# XTX.net
KiCad netlist of a schematic drawn in Altium Designer
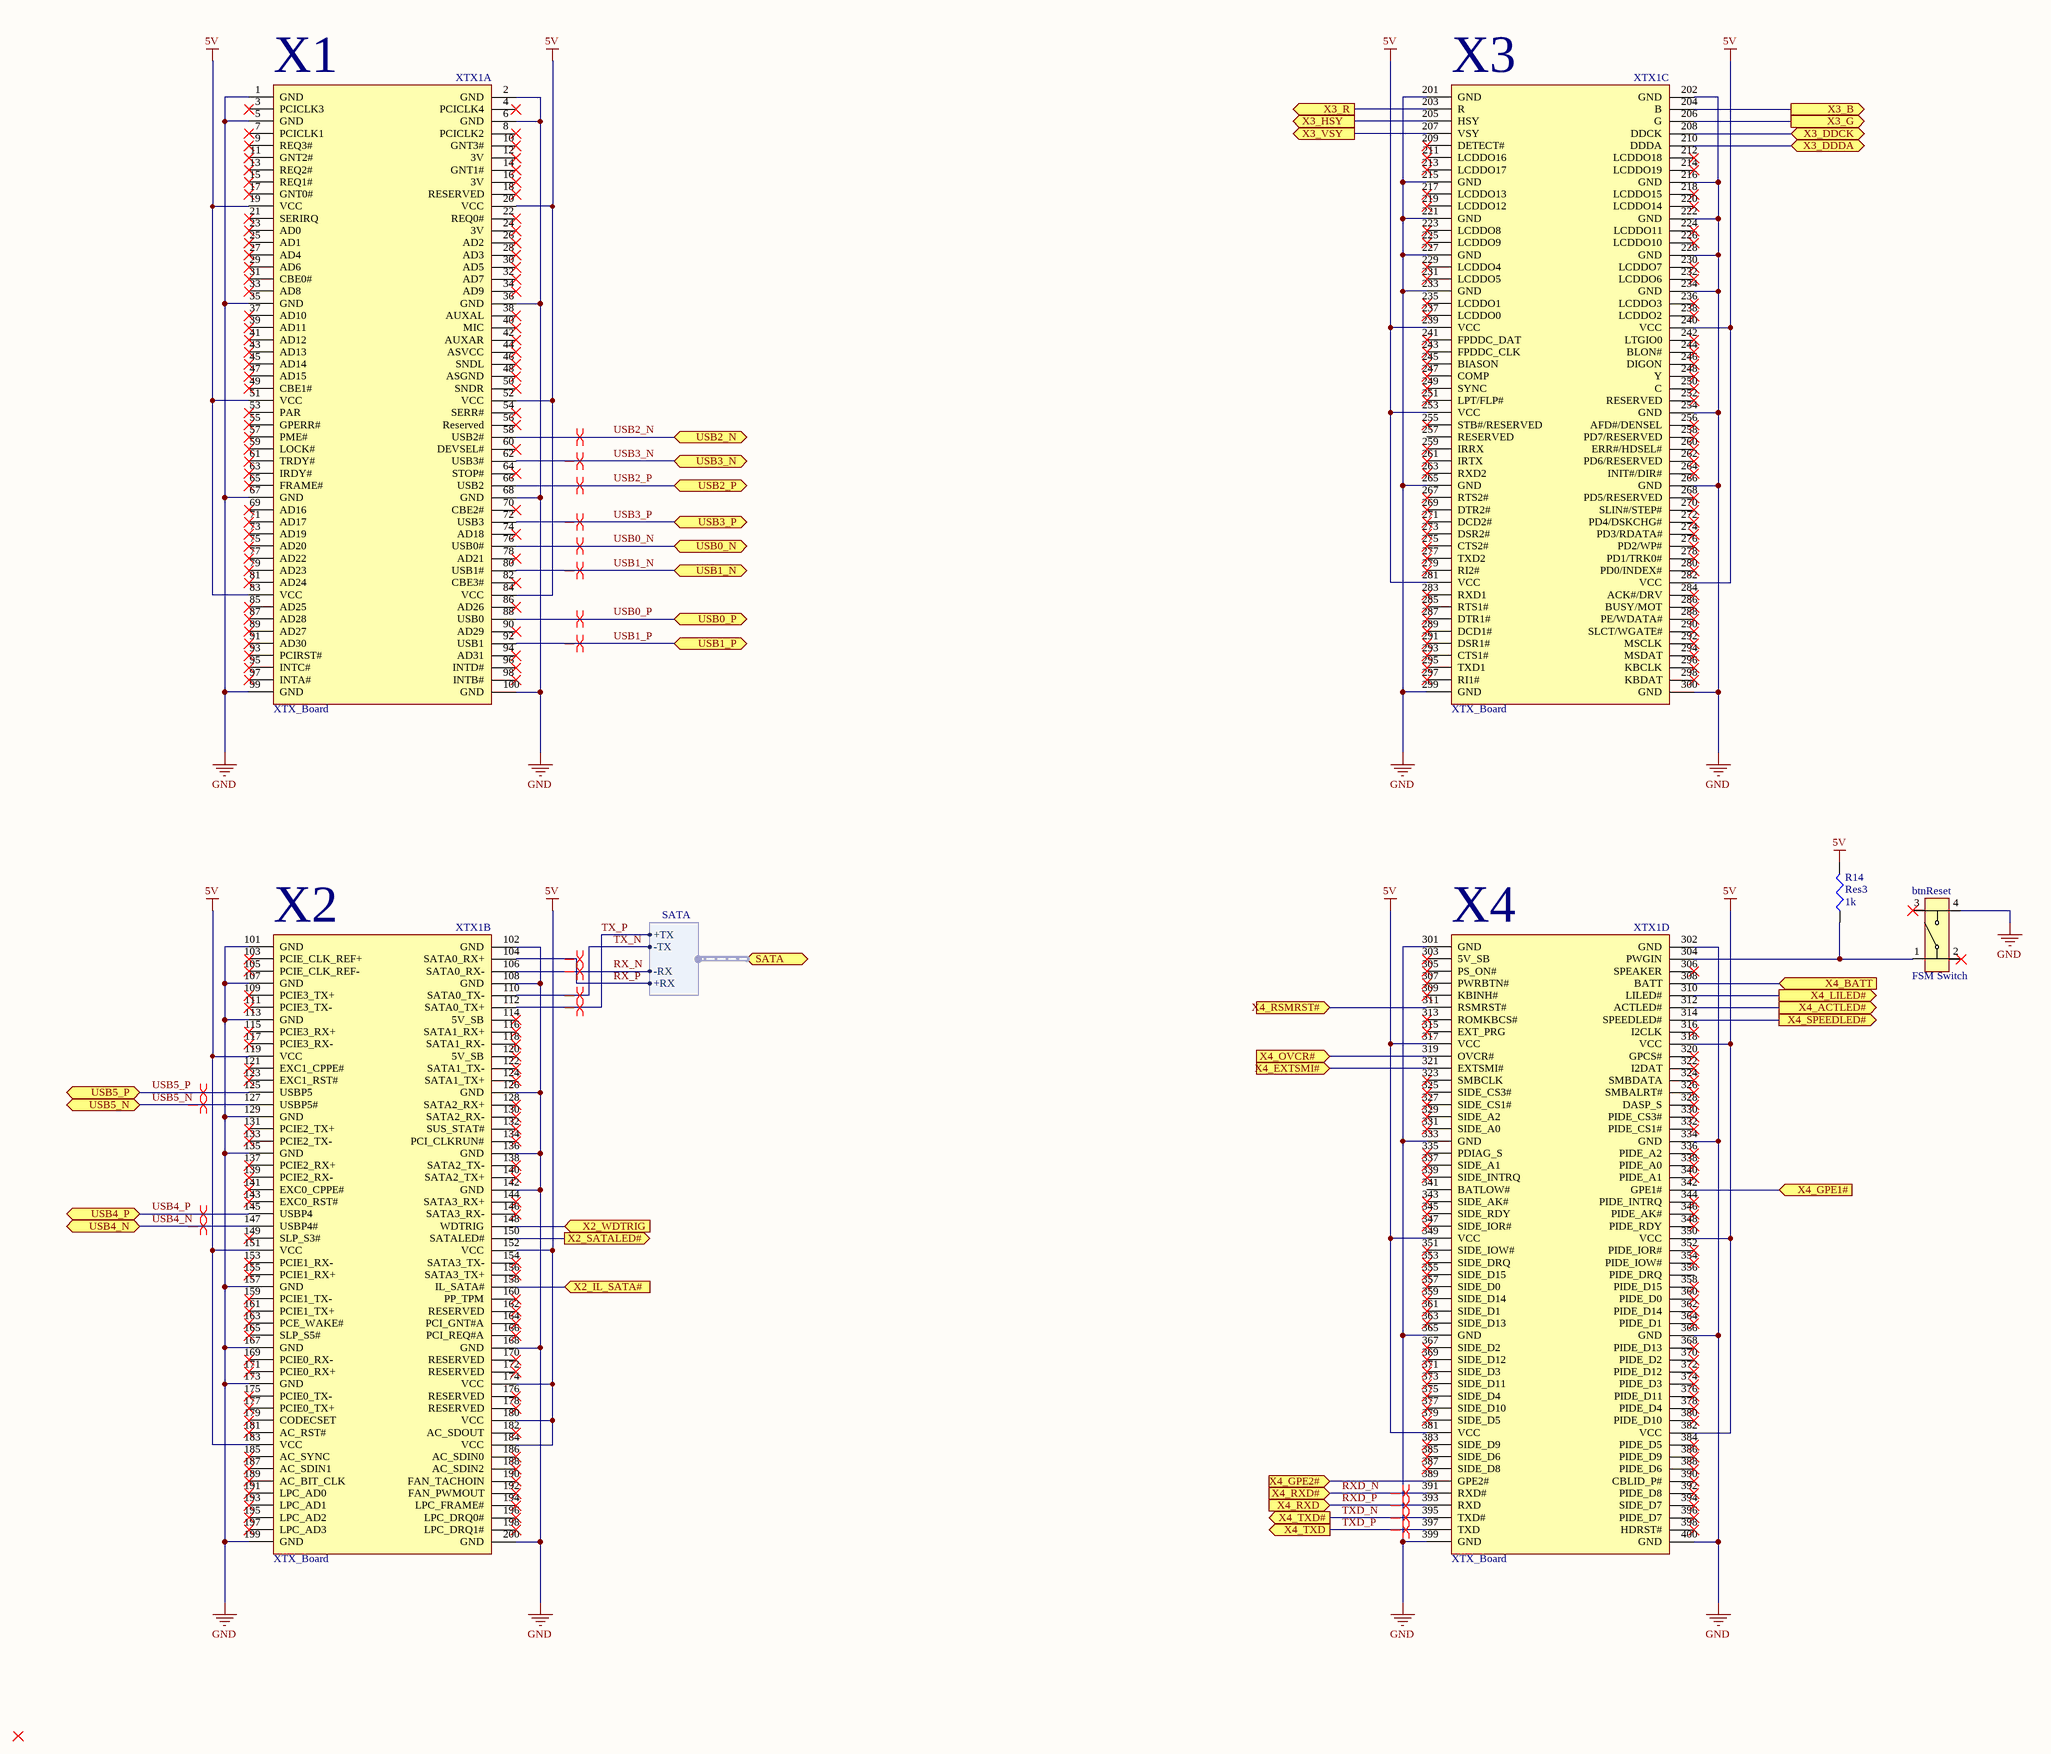
[diagram p0: XTX.SchDoc]

(export (version "E")
  (design (tool "Eeschema 10.0.6"))
  (components
    (comp (ref "btnReset")
      (value "FSM Switch")
      (footprint "FSM4JH")
      (description "FSM 6mm Series Switch")
      (libsource (lib "Buttons") (part "FSM Switch"))
    )
    (comp (ref "R14")
      (value "Res3")
      (footprint "J1-0603")
      (description "Resistor")
      (fields (field (name "ALTIUM_VALUE") "1k") (field (name "PUBLISHER") "Altium Limited"))
      (libsource (lib "Miscellaneous Devices") (part "Res3"))
    )
    (comp (ref "XTX1") (value "XTX_Board") (footprint "XTX_Board") (libsource (lib "XTX") (part "XTX_Board")))
  )
  (nets
    (net (code "2") (name "/RXD_N") (class "Default")
      (node (ref "XTX1") (pin "391") (pinfunction "RXD#_391") (pintype "passive"))
    )
    (net (code "3") (name "/RXD_P") (class "Default")
      (node (ref "XTX1") (pin "393") (pinfunction "RXD_393") (pintype "passive"))
    )
    (net (code "4") (name "/RX_N") (class "Default")
      (node (ref "XTX1") (pin "106") (pinfunction "SATA0_RX-_106") (pintype "passive"))
    )
    (net (code "5") (name "/RX_P") (class "Default")
      (node (ref "XTX1") (pin "104") (pinfunction "SATA0_RX+_104") (pintype "passive"))
    )
    (net (code "6") (name "/TXD_N") (class "Default")
      (node (ref "XTX1") (pin "395") (pinfunction "TXD#_395") (pintype "passive"))
    )
    (net (code "7") (name "/TXD_P") (class "Default")
      (node (ref "XTX1") (pin "397") (pinfunction "TXD_397") (pintype "passive"))
    )
    (net (code "8") (name "/TX_N") (class "Default")
      (node (ref "XTX1") (pin "110") (pinfunction "SATA0_TX-_110") (pintype "passive"))
    )
    (net (code "9") (name "/TX_P") (class "Default")
      (node (ref "XTX1") (pin "112") (pinfunction "SATA0_TX+_112") (pintype "passive"))
    )
    (net (code "10") (name "/USB0_N") (class "Default")
      (node (ref "XTX1") (pin "76") (pinfunction "USB0#_76") (pintype "passive"))
    )
    (net (code "11") (name "/USB0_P") (class "Default")
      (node (ref "XTX1") (pin "88") (pinfunction "USB0_88") (pintype "passive"))
    )
    (net (code "12") (name "/USB1_N") (class "Default")
      (node (ref "XTX1") (pin "80") (pinfunction "USB1#_80") (pintype "passive"))
    )
    (net (code "13") (name "/USB1_P") (class "Default")
      (node (ref "XTX1") (pin "92") (pinfunction "USB1_92") (pintype "passive"))
    )
    (net (code "14") (name "/USB2_N") (class "Default")
      (node (ref "XTX1") (pin "58") (pinfunction "USB2#_58") (pintype "passive"))
    )
    (net (code "15") (name "/USB2_P") (class "Default")
      (node (ref "XTX1") (pin "66") (pinfunction "USB2_66") (pintype "passive"))
    )
    (net (code "16") (name "/USB3_N") (class "Default")
      (node (ref "XTX1") (pin "62") (pinfunction "USB3#_62") (pintype "passive"))
    )
    (net (code "17") (name "/USB3_P") (class "Default")
      (node (ref "XTX1") (pin "72") (pinfunction "USB3_72") (pintype "passive"))
    )
    (net (code "18") (name "/USB4_N") (class "Default")
      (node (ref "XTX1") (pin "147") (pinfunction "USBP4#_147") (pintype "passive"))
    )
    (net (code "19") (name "/USB4_P") (class "Default")
      (node (ref "XTX1") (pin "145") (pinfunction "USBP4_145") (pintype "passive"))
    )
    (net (code "20") (name "/USB5_N") (class "Default")
      (node (ref "XTX1") (pin "127") (pinfunction "USBP5#_127") (pintype "passive"))
    )
    (net (code "21") (name "/USB5_P") (class "Default")
      (node (ref "XTX1") (pin "125") (pinfunction "USBP5_125") (pintype "passive"))
    )
    (net (code "22") (name "/X2_IL_SATA#") (class "Default")
      (node (ref "XTX1") (pin "158") (pinfunction "IL_SATA#_158") (pintype "passive"))
    )
    (net (code "23") (name "/X2_SATALED#") (class "Default")
      (node (ref "XTX1") (pin "150") (pinfunction "SATALED#_150") (pintype "passive"))
    )
    (net (code "24") (name "/X2_WDTRIG") (class "Default")
      (node (ref "XTX1") (pin "148") (pinfunction "WDTRIG_148") (pintype "passive"))
    )
    (net (code "25") (name "/X3_B") (class "Default")
      (node (ref "XTX1") (pin "204") (pinfunction "B_204") (pintype "passive"))
    )
    (net (code "26") (name "/X3_DDCK") (class "Default")
      (node (ref "XTX1") (pin "208") (pinfunction "DDCK_208") (pintype "passive"))
    )
    (net (code "27") (name "/X3_DDDA") (class "Default")
      (node (ref "XTX1") (pin "210") (pinfunction "DDDA_210") (pintype "passive"))
    )
    (net (code "28") (name "/X3_G") (class "Default")
      (node (ref "XTX1") (pin "206") (pinfunction "G_206") (pintype "passive"))
    )
    (net (code "29") (name "/X3_HSY") (class "Default")
      (node (ref "XTX1") (pin "205") (pinfunction "HSY_205") (pintype "passive"))
    )
    (net (code "30") (name "/X3_R") (class "Default")
      (node (ref "XTX1") (pin "203") (pinfunction "R_203") (pintype "passive"))
    )
    (net (code "31") (name "/X3_VSY") (class "Default")
      (node (ref "XTX1") (pin "207") (pinfunction "VSY_207") (pintype "passive"))
    )
    (net (code "32") (name "/X4_ACTLED#") (class "Default")
      (node (ref "XTX1") (pin "312") (pinfunction "ACTLED#_312") (pintype "passive"))
    )
    (net (code "33") (name "/X4_BATT") (class "Default")
      (node (ref "XTX1") (pin "308") (pinfunction "BATT_308") (pintype "passive"))
    )
    (net (code "34") (name "/X4_EXTSMI#") (class "Default")
      (node (ref "XTX1") (pin "321") (pinfunction "EXTSMI#_321") (pintype "passive"))
    )
    (net (code "35") (name "/X4_GPE1#") (class "Default")
      (node (ref "XTX1") (pin "342") (pinfunction "GPE1#_342") (pintype "passive"))
    )
    (net (code "36") (name "/X4_GPE2#") (class "Default")
      (node (ref "XTX1") (pin "389") (pinfunction "GPE2#_389") (pintype "passive"))
    )
    (net (code "37") (name "/X4_LILED#") (class "Default")
      (node (ref "XTX1") (pin "310") (pinfunction "LILED#_310") (pintype "passive"))
    )
    (net (code "38") (name "/X4_OVCR#") (class "Default")
      (node (ref "XTX1") (pin "319") (pinfunction "OVCR#_319") (pintype "passive"))
    )
    (net (code "39") (name "/X4_RSMRST#") (class "Default")
      (node (ref "XTX1") (pin "311") (pinfunction "RSMRST#_311") (pintype "passive"))
    )
    (net (code "40") (name "/X4_SPEEDLED#") (class "Default")
      (node (ref "XTX1") (pin "314") (pinfunction "SPEEDLED#_314") (pintype "passive"))
    )
    (net (code "42") (name "5V") (class "Default")
      (node (ref "R14") (pin "2") (pinfunction "2_2") (pintype "passive"))
      (node (ref "XTX1") (pin "119") (pinfunction "VCC_119") (pintype "passive"))
      (node (ref "XTX1") (pin "151") (pinfunction "VCC_151") (pintype "passive"))
      (node (ref "XTX1") (pin "152") (pinfunction "VCC_152") (pintype "passive"))
      (node (ref "XTX1") (pin "174") (pinfunction "VCC_174") (pintype "passive"))
      (node (ref "XTX1") (pin "180") (pinfunction "VCC_180") (pintype "passive"))
      (node (ref "XTX1") (pin "183") (pinfunction "VCC_183") (pintype "passive"))
      (node (ref "XTX1") (pin "184") (pinfunction "VCC_184") (pintype "passive"))
      (node (ref "XTX1") (pin "19") (pinfunction "VCC_19") (pintype "passive"))
      (node (ref "XTX1") (pin "20") (pinfunction "VCC_20") (pintype "passive"))
      (node (ref "XTX1") (pin "239") (pinfunction "VCC_239") (pintype "passive"))
      (node (ref "XTX1") (pin "240") (pinfunction "VCC_240") (pintype "passive"))
      (node (ref "XTX1") (pin "253") (pinfunction "VCC_253") (pintype "passive"))
      (node (ref "XTX1") (pin "281") (pinfunction "VCC_281") (pintype "passive"))
      (node (ref "XTX1") (pin "282") (pinfunction "VCC_282") (pintype "passive"))
      (node (ref "XTX1") (pin "317") (pinfunction "VCC_317") (pintype "passive"))
      (node (ref "XTX1") (pin "318") (pinfunction "VCC_318") (pintype "passive"))
      (node (ref "XTX1") (pin "349") (pinfunction "VCC_349") (pintype "passive"))
      (node (ref "XTX1") (pin "350") (pinfunction "VCC_350") (pintype "passive"))
      (node (ref "XTX1") (pin "381") (pinfunction "VCC_381") (pintype "passive"))
      (node (ref "XTX1") (pin "382") (pinfunction "VCC_382") (pintype "passive"))
      (node (ref "XTX1") (pin "51") (pinfunction "VCC_51") (pintype "passive"))
      (node (ref "XTX1") (pin "52") (pinfunction "VCC_52") (pintype "passive"))
      (node (ref "XTX1") (pin "83") (pinfunction "VCC_83") (pintype "passive"))
      (node (ref "XTX1") (pin "84") (pinfunction "VCC_84") (pintype "passive"))
    )
    (net (code "43") (name "GND") (class "Default")
      (node (ref "XTX1") (pin "1") (pinfunction "GND_1") (pintype "passive"))
      (node (ref "XTX1") (pin "100") (pinfunction "GND_100") (pintype "passive"))
      (node (ref "XTX1") (pin "101") (pinfunction "GND_101") (pintype "passive"))
      (node (ref "XTX1") (pin "102") (pinfunction "GND_102") (pintype "passive"))
      (node (ref "XTX1") (pin "107") (pinfunction "GND_107") (pintype "passive"))
      (node (ref "XTX1") (pin "108") (pinfunction "GND_108") (pintype "passive"))
      (node (ref "XTX1") (pin "113") (pinfunction "GND_113") (pintype "passive"))
      (node (ref "XTX1") (pin "126") (pinfunction "GND_126") (pintype "passive"))
      (node (ref "XTX1") (pin "129") (pinfunction "GND_129") (pintype "passive"))
      (node (ref "XTX1") (pin "135") (pinfunction "GND_135") (pintype "passive"))
      (node (ref "XTX1") (pin "136") (pinfunction "GND_136") (pintype "passive"))
      (node (ref "XTX1") (pin "142") (pinfunction "GND_142") (pintype "passive"))
      (node (ref "XTX1") (pin "157") (pinfunction "GND_157") (pintype "passive"))
      (node (ref "XTX1") (pin "167") (pinfunction "GND_167") (pintype "passive"))
      (node (ref "XTX1") (pin "168") (pinfunction "GND_168") (pintype "passive"))
      (node (ref "XTX1") (pin "173") (pinfunction "GND_173") (pintype "passive"))
      (node (ref "XTX1") (pin "199") (pinfunction "GND_199") (pintype "passive"))
      (node (ref "XTX1") (pin "2") (pinfunction "GND_2") (pintype "passive"))
      (node (ref "XTX1") (pin "200") (pinfunction "GND_200") (pintype "passive"))
      (node (ref "XTX1") (pin "201") (pinfunction "GND_201") (pintype "passive"))
      (node (ref "XTX1") (pin "202") (pinfunction "GND_202") (pintype "passive"))
      (node (ref "XTX1") (pin "215") (pinfunction "GND_215") (pintype "passive"))
      (node (ref "XTX1") (pin "216") (pinfunction "GND_216") (pintype "passive"))
      (node (ref "XTX1") (pin "221") (pinfunction "GND_221") (pintype "passive"))
      (node (ref "XTX1") (pin "222") (pinfunction "GND_222") (pintype "passive"))
      (node (ref "XTX1") (pin "227") (pinfunction "GND_227") (pintype "passive"))
      (node (ref "XTX1") (pin "228") (pinfunction "GND_228") (pintype "passive"))
      (node (ref "XTX1") (pin "233") (pinfunction "GND_233") (pintype "passive"))
      (node (ref "XTX1") (pin "234") (pinfunction "GND_234") (pintype "passive"))
      (node (ref "XTX1") (pin "254") (pinfunction "GND_254") (pintype "passive"))
      (node (ref "XTX1") (pin "265") (pinfunction "GND_265") (pintype "passive"))
      (node (ref "XTX1") (pin "266") (pinfunction "GND_266") (pintype "passive"))
      (node (ref "XTX1") (pin "299") (pinfunction "GND_299") (pintype "passive"))
      (node (ref "XTX1") (pin "300") (pinfunction "GND_300") (pintype "passive"))
      (node (ref "XTX1") (pin "301") (pinfunction "GND_301") (pintype "passive"))
      (node (ref "XTX1") (pin "302") (pinfunction "GND_302") (pintype "passive"))
      (node (ref "XTX1") (pin "333") (pinfunction "GND_333") (pintype "passive"))
      (node (ref "XTX1") (pin "334") (pinfunction "GND_334") (pintype "passive"))
      (node (ref "XTX1") (pin "35") (pinfunction "GND_35") (pintype "passive"))
      (node (ref "XTX1") (pin "36") (pinfunction "GND_36") (pintype "passive"))
      (node (ref "XTX1") (pin "365") (pinfunction "GND_365") (pintype "passive"))
      (node (ref "XTX1") (pin "366") (pinfunction "GND_366") (pintype "passive"))
      (node (ref "XTX1") (pin "399") (pinfunction "GND_399") (pintype "passive"))
      (node (ref "XTX1") (pin "400") (pinfunction "GND_400") (pintype "passive"))
      (node (ref "XTX1") (pin "5") (pinfunction "GND_5") (pintype "passive"))
      (node (ref "XTX1") (pin "6") (pinfunction "GND_6") (pintype "passive"))
      (node (ref "XTX1") (pin "67") (pinfunction "GND_67") (pintype "passive"))
      (node (ref "XTX1") (pin "68") (pinfunction "GND_68") (pintype "passive"))
      (node (ref "XTX1") (pin "99") (pinfunction "GND_99") (pintype "passive"))
      (node (ref "btnReset") (pin "4") (pinfunction "4_4") (pintype "passive"))
    )
    (net (code "44") (name "Net-(XTX1D-PWGIN)") (class "Default")
      (node (ref "R14") (pin "1") (pinfunction "1_1") (pintype "passive"))
      (node (ref "XTX1") (pin "304") (pinfunction "PWGIN_304") (pintype "passive"))
      (node (ref "btnReset") (pin "1") (pinfunction "1_1") (pintype "passive"))
    )
    (net (code "45") (name "unconnected-(XTX1A-3V-Pad12)") (class "Default")
      (node (ref "XTX1") (pin "12") (pinfunction "3V_12") (pintype "passive+no_connect"))
    )
    (net (code "46") (name "unconnected-(XTX1A-3V-Pad16)") (class "Default")
      (node (ref "XTX1") (pin "16") (pinfunction "3V_16") (pintype "passive+no_connect"))
    )
    (net (code "47") (name "unconnected-(XTX1A-3V-Pad24)") (class "Default")
      (node (ref "XTX1") (pin "24") (pinfunction "3V_24") (pintype "passive+no_connect"))
    )
    (net (code "48") (name "unconnected-(XTX1A-AD0-Pad23)") (class "Default")
      (node (ref "XTX1") (pin "23") (pinfunction "AD0_23") (pintype "passive+no_connect"))
    )
    (net (code "49") (name "unconnected-(XTX1A-AD1-Pad25)") (class "Default")
      (node (ref "XTX1") (pin "25") (pinfunction "AD1_25") (pintype "passive+no_connect"))
    )
    (net (code "50") (name "unconnected-(XTX1A-AD2-Pad26)") (class "Default")
      (node (ref "XTX1") (pin "26") (pinfunction "AD2_26") (pintype "passive+no_connect"))
    )
    (net (code "51") (name "unconnected-(XTX1A-AD3-Pad28)") (class "Default")
      (node (ref "XTX1") (pin "28") (pinfunction "AD3_28") (pintype "passive+no_connect"))
    )
    (net (code "52") (name "unconnected-(XTX1A-AD4-Pad27)") (class "Default")
      (node (ref "XTX1") (pin "27") (pinfunction "AD4_27") (pintype "passive+no_connect"))
    )
    (net (code "53") (name "unconnected-(XTX1A-AD5-Pad30)") (class "Default")
      (node (ref "XTX1") (pin "30") (pinfunction "AD5_30") (pintype "passive+no_connect"))
    )
    (net (code "54") (name "unconnected-(XTX1A-AD6-Pad29)") (class "Default")
      (node (ref "XTX1") (pin "29") (pinfunction "AD6_29") (pintype "passive+no_connect"))
    )
    (net (code "55") (name "unconnected-(XTX1A-AD7-Pad32)") (class "Default")
      (node (ref "XTX1") (pin "32") (pinfunction "AD7_32") (pintype "passive+no_connect"))
    )
    (net (code "56") (name "unconnected-(XTX1A-AD8-Pad33)") (class "Default")
      (node (ref "XTX1") (pin "33") (pinfunction "AD8_33") (pintype "passive+no_connect"))
    )
    (net (code "57") (name "unconnected-(XTX1A-AD9-Pad34)") (class "Default")
      (node (ref "XTX1") (pin "34") (pinfunction "AD9_34") (pintype "passive+no_connect"))
    )
    (net (code "58") (name "unconnected-(XTX1A-AD10-Pad37)") (class "Default")
      (node (ref "XTX1") (pin "37") (pinfunction "AD10_37") (pintype "passive+no_connect"))
    )
    (net (code "59") (name "unconnected-(XTX1A-AD11-Pad39)") (class "Default")
      (node (ref "XTX1") (pin "39") (pinfunction "AD11_39") (pintype "passive+no_connect"))
    )
    (net (code "60") (name "unconnected-(XTX1A-AD12-Pad41)") (class "Default")
      (node (ref "XTX1") (pin "41") (pinfunction "AD12_41") (pintype "passive+no_connect"))
    )
    (net (code "61") (name "unconnected-(XTX1A-AD13-Pad43)") (class "Default")
      (node (ref "XTX1") (pin "43") (pinfunction "AD13_43") (pintype "passive+no_connect"))
    )
    (net (code "62") (name "unconnected-(XTX1A-AD14-Pad45)") (class "Default")
      (node (ref "XTX1") (pin "45") (pinfunction "AD14_45") (pintype "passive+no_connect"))
    )
    (net (code "63") (name "unconnected-(XTX1A-AD15-Pad47)") (class "Default")
      (node (ref "XTX1") (pin "47") (pinfunction "AD15_47") (pintype "passive+no_connect"))
    )
    (net (code "64") (name "unconnected-(XTX1A-AD16-Pad69)") (class "Default")
      (node (ref "XTX1") (pin "69") (pinfunction "AD16_69") (pintype "passive+no_connect"))
    )
    (net (code "65") (name "unconnected-(XTX1A-AD17-Pad71)") (class "Default")
      (node (ref "XTX1") (pin "71") (pinfunction "AD17_71") (pintype "passive+no_connect"))
    )
    (net (code "66") (name "unconnected-(XTX1A-AD18-Pad74)") (class "Default")
      (node (ref "XTX1") (pin "74") (pinfunction "AD18_74") (pintype "passive+no_connect"))
    )
    (net (code "67") (name "unconnected-(XTX1A-AD19-Pad73)") (class "Default")
      (node (ref "XTX1") (pin "73") (pinfunction "AD19_73") (pintype "passive+no_connect"))
    )
    (net (code "68") (name "unconnected-(XTX1A-AD20-Pad75)") (class "Default")
      (node (ref "XTX1") (pin "75") (pinfunction "AD20_75") (pintype "passive+no_connect"))
    )
    (net (code "69") (name "unconnected-(XTX1A-AD21-Pad78)") (class "Default")
      (node (ref "XTX1") (pin "78") (pinfunction "AD21_78") (pintype "passive+no_connect"))
    )
    (net (code "70") (name "unconnected-(XTX1A-AD22-Pad77)") (class "Default")
      (node (ref "XTX1") (pin "77") (pinfunction "AD22_77") (pintype "passive+no_connect"))
    )
    (net (code "71") (name "unconnected-(XTX1A-AD23-Pad79)") (class "Default")
      (node (ref "XTX1") (pin "79") (pinfunction "AD23_79") (pintype "passive+no_connect"))
    )
    (net (code "72") (name "unconnected-(XTX1A-AD24-Pad81)") (class "Default")
      (node (ref "XTX1") (pin "81") (pinfunction "AD24_81") (pintype "passive+no_connect"))
    )
    (net (code "73") (name "unconnected-(XTX1A-AD25-Pad85)") (class "Default")
      (node (ref "XTX1") (pin "85") (pinfunction "AD25_85") (pintype "passive+no_connect"))
    )
    (net (code "74") (name "unconnected-(XTX1A-AD26-Pad86)") (class "Default")
      (node (ref "XTX1") (pin "86") (pinfunction "AD26_86") (pintype "passive+no_connect"))
    )
    (net (code "75") (name "unconnected-(XTX1A-AD27-Pad89)") (class "Default")
      (node (ref "XTX1") (pin "89") (pinfunction "AD27_89") (pintype "passive+no_connect"))
    )
    (net (code "76") (name "unconnected-(XTX1A-AD28-Pad87)") (class "Default")
      (node (ref "XTX1") (pin "87") (pinfunction "AD28_87") (pintype "passive+no_connect"))
    )
    (net (code "77") (name "unconnected-(XTX1A-AD29-Pad90)") (class "Default")
      (node (ref "XTX1") (pin "90") (pinfunction "AD29_90") (pintype "passive+no_connect"))
    )
    (net (code "78") (name "unconnected-(XTX1A-AD30-Pad91)") (class "Default")
      (node (ref "XTX1") (pin "91") (pinfunction "AD30_91") (pintype "passive+no_connect"))
    )
    (net (code "79") (name "unconnected-(XTX1A-AD31-Pad94)") (class "Default")
      (node (ref "XTX1") (pin "94") (pinfunction "AD31_94") (pintype "passive+no_connect"))
    )
    (net (code "80") (name "unconnected-(XTX1A-ASGND-Pad48)") (class "Default")
      (node (ref "XTX1") (pin "48") (pinfunction "ASGND_48") (pintype "passive+no_connect"))
    )
    (net (code "81") (name "unconnected-(XTX1A-ASVCC-Pad44)") (class "Default")
      (node (ref "XTX1") (pin "44") (pinfunction "ASVCC_44") (pintype "passive+no_connect"))
    )
    (net (code "82") (name "unconnected-(XTX1A-AUXAL-Pad38)") (class "Default")
      (node (ref "XTX1") (pin "38") (pinfunction "AUXAL_38") (pintype "passive+no_connect"))
    )
    (net (code "83") (name "unconnected-(XTX1A-AUXAR-Pad42)") (class "Default")
      (node (ref "XTX1") (pin "42") (pinfunction "AUXAR_42") (pintype "passive+no_connect"))
    )
    (net (code "84") (name "unconnected-(XTX1A-CBE0#-Pad31)") (class "Default")
      (node (ref "XTX1") (pin "31") (pinfunction "CBE0#_31") (pintype "passive+no_connect"))
    )
    (net (code "85") (name "unconnected-(XTX1A-CBE1#-Pad49)") (class "Default")
      (node (ref "XTX1") (pin "49") (pinfunction "CBE1#_49") (pintype "passive+no_connect"))
    )
    (net (code "86") (name "unconnected-(XTX1A-CBE2#-Pad70)") (class "Default")
      (node (ref "XTX1") (pin "70") (pinfunction "CBE2#_70") (pintype "passive+no_connect"))
    )
    (net (code "87") (name "unconnected-(XTX1A-CBE3#-Pad82)") (class "Default")
      (node (ref "XTX1") (pin "82") (pinfunction "CBE3#_82") (pintype "passive+no_connect"))
    )
    (net (code "88") (name "unconnected-(XTX1A-DEVSEL#-Pad60)") (class "Default")
      (node (ref "XTX1") (pin "60") (pinfunction "DEVSEL#_60") (pintype "passive+no_connect"))
    )
    (net (code "89") (name "unconnected-(XTX1A-FRAME#-Pad65)") (class "Default")
      (node (ref "XTX1") (pin "65") (pinfunction "FRAME#_65") (pintype "passive+no_connect"))
    )
    (net (code "90") (name "unconnected-(XTX1A-GNT0#-Pad17)") (class "Default")
      (node (ref "XTX1") (pin "17") (pinfunction "GNT0#_17") (pintype "passive+no_connect"))
    )
    (net (code "91") (name "unconnected-(XTX1A-GNT1#-Pad14)") (class "Default")
      (node (ref "XTX1") (pin "14") (pinfunction "GNT1#_14") (pintype "passive+no_connect"))
    )
    (net (code "92") (name "unconnected-(XTX1A-GNT2#-Pad11)") (class "Default")
      (node (ref "XTX1") (pin "11") (pinfunction "GNT2#_11") (pintype "passive+no_connect"))
    )
    (net (code "93") (name "unconnected-(XTX1A-GNT3#-Pad10)") (class "Default")
      (node (ref "XTX1") (pin "10") (pinfunction "GNT3#_10") (pintype "passive+no_connect"))
    )
    (net (code "94") (name "unconnected-(XTX1A-GPERR#-Pad55)") (class "Default")
      (node (ref "XTX1") (pin "55") (pinfunction "GPERR#_55") (pintype "passive+no_connect"))
    )
    (net (code "95") (name "unconnected-(XTX1A-INTA#-Pad97)") (class "Default")
      (node (ref "XTX1") (pin "97") (pinfunction "INTA#_97") (pintype "passive+no_connect"))
    )
    (net (code "96") (name "unconnected-(XTX1A-INTB#-Pad98)") (class "Default")
      (node (ref "XTX1") (pin "98") (pinfunction "INTB#_98") (pintype "passive+no_connect"))
    )
    (net (code "97") (name "unconnected-(XTX1A-INTC#-Pad95)") (class "Default")
      (node (ref "XTX1") (pin "95") (pinfunction "INTC#_95") (pintype "passive+no_connect"))
    )
    (net (code "98") (name "unconnected-(XTX1A-INTD#-Pad96)") (class "Default")
      (node (ref "XTX1") (pin "96") (pinfunction "INTD#_96") (pintype "passive+no_connect"))
    )
    (net (code "99") (name "unconnected-(XTX1A-IRDY#-Pad63)") (class "Default")
      (node (ref "XTX1") (pin "63") (pinfunction "IRDY#_63") (pintype "passive+no_connect"))
    )
    (net (code "100") (name "unconnected-(XTX1A-LOCK#-Pad59)") (class "Default")
      (node (ref "XTX1") (pin "59") (pinfunction "LOCK#_59") (pintype "passive+no_connect"))
    )
    (net (code "101") (name "unconnected-(XTX1A-MIC-Pad40)") (class "Default")
      (node (ref "XTX1") (pin "40") (pinfunction "MIC_40") (pintype "passive+no_connect"))
    )
    (net (code "102") (name "unconnected-(XTX1A-PAR-Pad53)") (class "Default")
      (node (ref "XTX1") (pin "53") (pinfunction "PAR_53") (pintype "passive+no_connect"))
    )
    (net (code "103") (name "unconnected-(XTX1A-PCICLK1-Pad7)") (class "Default")
      (node (ref "XTX1") (pin "7") (pinfunction "PCICLK1_7") (pintype "passive+no_connect"))
    )
    (net (code "104") (name "unconnected-(XTX1A-PCICLK2-Pad8)") (class "Default")
      (node (ref "XTX1") (pin "8") (pinfunction "PCICLK2_8") (pintype "passive+no_connect"))
    )
    (net (code "105") (name "unconnected-(XTX1A-PCICLK3-Pad3)") (class "Default")
      (node (ref "XTX1") (pin "3") (pinfunction "PCICLK3_3") (pintype "passive+no_connect"))
    )
    (net (code "106") (name "unconnected-(XTX1A-PCICLK4-Pad4)") (class "Default")
      (node (ref "XTX1") (pin "4") (pinfunction "PCICLK4_4") (pintype "passive+no_connect"))
    )
    (net (code "107") (name "unconnected-(XTX1A-PCIRST#-Pad93)") (class "Default")
      (node (ref "XTX1") (pin "93") (pinfunction "PCIRST#_93") (pintype "passive+no_connect"))
    )
    (net (code "108") (name "unconnected-(XTX1A-PME#-Pad57)") (class "Default")
      (node (ref "XTX1") (pin "57") (pinfunction "PME#_57") (pintype "passive+no_connect"))
    )
    (net (code "109") (name "unconnected-(XTX1A-REQ0#-Pad22)") (class "Default")
      (node (ref "XTX1") (pin "22") (pinfunction "REQ0#_22") (pintype "passive+no_connect"))
    )
    (net (code "110") (name "unconnected-(XTX1A-REQ1#-Pad15)") (class "Default")
      (node (ref "XTX1") (pin "15") (pinfunction "REQ1#_15") (pintype "passive+no_connect"))
    )
    (net (code "111") (name "unconnected-(XTX1A-REQ2#-Pad13)") (class "Default")
      (node (ref "XTX1") (pin "13") (pinfunction "REQ2#_13") (pintype "passive+no_connect"))
    )
    (net (code "112") (name "unconnected-(XTX1A-REQ3#-Pad9)") (class "Default")
      (node (ref "XTX1") (pin "9") (pinfunction "REQ3#_9") (pintype "passive+no_connect"))
    )
    (net (code "113") (name "unconnected-(XTX1A-RESERVED-Pad18)") (class "Default")
      (node (ref "XTX1") (pin "18") (pinfunction "RESERVED_18") (pintype "passive+no_connect"))
    )
    (net (code "114") (name "unconnected-(XTX1A-Reserved-Pad56)") (class "Default")
      (node (ref "XTX1") (pin "56") (pinfunction "Reserved_56") (pintype "passive+no_connect"))
    )
    (net (code "115") (name "unconnected-(XTX1A-SERIRQ-Pad21)") (class "Default")
      (node (ref "XTX1") (pin "21") (pinfunction "SERIRQ_21") (pintype "passive+no_connect"))
    )
    (net (code "116") (name "unconnected-(XTX1A-SERR#-Pad54)") (class "Default")
      (node (ref "XTX1") (pin "54") (pinfunction "SERR#_54") (pintype "passive+no_connect"))
    )
    (net (code "117") (name "unconnected-(XTX1A-SNDL-Pad46)") (class "Default")
      (node (ref "XTX1") (pin "46") (pinfunction "SNDL_46") (pintype "passive+no_connect"))
    )
    (net (code "118") (name "unconnected-(XTX1A-SNDR-Pad50)") (class "Default")
      (node (ref "XTX1") (pin "50") (pinfunction "SNDR_50") (pintype "passive+no_connect"))
    )
    (net (code "119") (name "unconnected-(XTX1A-STOP#-Pad64)") (class "Default")
      (node (ref "XTX1") (pin "64") (pinfunction "STOP#_64") (pintype "passive+no_connect"))
    )
    (net (code "120") (name "unconnected-(XTX1A-TRDY#-Pad61)") (class "Default")
      (node (ref "XTX1") (pin "61") (pinfunction "TRDY#_61") (pintype "passive+no_connect"))
    )
    (net (code "121") (name "unconnected-(XTX1B-5V_SB-Pad114)") (class "Default")
      (node (ref "XTX1") (pin "114") (pinfunction "5V_SB_114") (pintype "passive+no_connect"))
    )
    (net (code "122") (name "unconnected-(XTX1B-5V_SB-Pad120)") (class "Default")
      (node (ref "XTX1") (pin "120") (pinfunction "5V_SB_120") (pintype "passive+no_connect"))
    )
    (net (code "123") (name "unconnected-(XTX1B-AC_BIT_CLK-Pad189)") (class "Default")
      (node (ref "XTX1") (pin "189") (pinfunction "AC_BIT_CLK_189") (pintype "passive+no_connect"))
    )
    (net (code "124") (name "unconnected-(XTX1B-AC_RST#-Pad181)") (class "Default")
      (node (ref "XTX1") (pin "181") (pinfunction "AC_RST#_181") (pintype "passive+no_connect"))
    )
    (net (code "125") (name "unconnected-(XTX1B-AC_SDIN0-Pad186)") (class "Default")
      (node (ref "XTX1") (pin "186") (pinfunction "AC_SDIN0_186") (pintype "passive+no_connect"))
    )
    (net (code "126") (name "unconnected-(XTX1B-AC_SDIN1-Pad187)") (class "Default")
      (node (ref "XTX1") (pin "187") (pinfunction "AC_SDIN1_187") (pintype "passive+no_connect"))
    )
    (net (code "127") (name "unconnected-(XTX1B-AC_SDIN2-Pad188)") (class "Default")
      (node (ref "XTX1") (pin "188") (pinfunction "AC_SDIN2_188") (pintype "passive+no_connect"))
    )
    (net (code "128") (name "unconnected-(XTX1B-AC_SDOUT-Pad182)") (class "Default")
      (node (ref "XTX1") (pin "182") (pinfunction "AC_SDOUT_182") (pintype "passive+no_connect"))
    )
    (net (code "129") (name "unconnected-(XTX1B-AC_SYNC-Pad185)") (class "Default")
      (node (ref "XTX1") (pin "185") (pinfunction "AC_SYNC_185") (pintype "passive+no_connect"))
    )
    (net (code "130") (name "unconnected-(XTX1B-CODECSET-Pad179)") (class "Default")
      (node (ref "XTX1") (pin "179") (pinfunction "CODECSET_179") (pintype "passive+no_connect"))
    )
    (net (code "131") (name "unconnected-(XTX1B-EXC0_CPPE#-Pad141)") (class "Default")
      (node (ref "XTX1") (pin "141") (pinfunction "EXC0_CPPE#_141") (pintype "passive+no_connect"))
    )
    (net (code "132") (name "unconnected-(XTX1B-EXC0_RST#-Pad143)") (class "Default")
      (node (ref "XTX1") (pin "143") (pinfunction "EXC0_RST#_143") (pintype "passive+no_connect"))
    )
    (net (code "133") (name "unconnected-(XTX1B-EXC1_CPPE#-Pad121)") (class "Default")
      (node (ref "XTX1") (pin "121") (pinfunction "EXC1_CPPE#_121") (pintype "passive+no_connect"))
    )
    (net (code "134") (name "unconnected-(XTX1B-EXC1_RST#-Pad123)") (class "Default")
      (node (ref "XTX1") (pin "123") (pinfunction "EXC1_RST#_123") (pintype "passive+no_connect"))
    )
    (net (code "135") (name "unconnected-(XTX1B-FAN_PWMOUT-Pad192)") (class "Default")
      (node (ref "XTX1") (pin "192") (pinfunction "FAN_PWMOUT_192") (pintype "passive+no_connect"))
    )
    (net (code "136") (name "unconnected-(XTX1B-FAN_TACHOIN-Pad190)") (class "Default")
      (node (ref "XTX1") (pin "190") (pinfunction "FAN_TACHOIN_190") (pintype "passive+no_connect"))
    )
    (net (code "137") (name "unconnected-(XTX1B-LPC_AD0-Pad191)") (class "Default")
      (node (ref "XTX1") (pin "191") (pinfunction "LPC_AD0_191") (pintype "passive+no_connect"))
    )
    (net (code "138") (name "unconnected-(XTX1B-LPC_AD1-Pad193)") (class "Default")
      (node (ref "XTX1") (pin "193") (pinfunction "LPC_AD1_193") (pintype "passive+no_connect"))
    )
    (net (code "139") (name "unconnected-(XTX1B-LPC_AD2-Pad195)") (class "Default")
      (node (ref "XTX1") (pin "195") (pinfunction "LPC_AD2_195") (pintype "passive+no_connect"))
    )
    (net (code "140") (name "unconnected-(XTX1B-LPC_AD3-Pad197)") (class "Default")
      (node (ref "XTX1") (pin "197") (pinfunction "LPC_AD3_197") (pintype "passive+no_connect"))
    )
    (net (code "141") (name "unconnected-(XTX1B-LPC_DRQ0#-Pad196)") (class "Default")
      (node (ref "XTX1") (pin "196") (pinfunction "LPC_DRQ0#_196") (pintype "passive+no_connect"))
    )
    (net (code "142") (name "unconnected-(XTX1B-LPC_DRQ1#-Pad198)") (class "Default")
      (node (ref "XTX1") (pin "198") (pinfunction "LPC_DRQ1#_198") (pintype "passive+no_connect"))
    )
    (net (code "143") (name "unconnected-(XTX1B-LPC_FRAME#-Pad194)") (class "Default")
      (node (ref "XTX1") (pin "194") (pinfunction "LPC_FRAME#_194") (pintype "passive+no_connect"))
    )
    (net (code "144") (name "unconnected-(XTX1B-PCE_WAKE#-Pad163)") (class "Default")
      (node (ref "XTX1") (pin "163") (pinfunction "PCE_WAKE#_163") (pintype "passive+no_connect"))
    )
    (net (code "145") (name "unconnected-(XTX1B-PCIE0_RX+-Pad171)") (class "Default")
      (node (ref "XTX1") (pin "171") (pinfunction "PCIE0_RX+_171") (pintype "passive+no_connect"))
    )
    (net (code "146") (name "unconnected-(XTX1B-PCIE0_RX--Pad169)") (class "Default")
      (node (ref "XTX1") (pin "169") (pinfunction "PCIE0_RX-_169") (pintype "passive+no_connect"))
    )
    (net (code "147") (name "unconnected-(XTX1B-PCIE0_TX+-Pad177)") (class "Default")
      (node (ref "XTX1") (pin "177") (pinfunction "PCIE0_TX+_177") (pintype "passive+no_connect"))
    )
    (net (code "148") (name "unconnected-(XTX1B-PCIE0_TX--Pad175)") (class "Default")
      (node (ref "XTX1") (pin "175") (pinfunction "PCIE0_TX-_175") (pintype "passive+no_connect"))
    )
    (net (code "149") (name "unconnected-(XTX1B-PCIE1_RX+-Pad155)") (class "Default")
      (node (ref "XTX1") (pin "155") (pinfunction "PCIE1_RX+_155") (pintype "passive+no_connect"))
    )
    (net (code "150") (name "unconnected-(XTX1B-PCIE1_RX--Pad153)") (class "Default")
      (node (ref "XTX1") (pin "153") (pinfunction "PCIE1_RX-_153") (pintype "passive+no_connect"))
    )
    (net (code "151") (name "unconnected-(XTX1B-PCIE1_TX+-Pad161)") (class "Default")
      (node (ref "XTX1") (pin "161") (pinfunction "PCIE1_TX+_161") (pintype "passive+no_connect"))
    )
    (net (code "152") (name "unconnected-(XTX1B-PCIE1_TX--Pad159)") (class "Default")
      (node (ref "XTX1") (pin "159") (pinfunction "PCIE1_TX-_159") (pintype "passive+no_connect"))
    )
    (net (code "153") (name "unconnected-(XTX1B-PCIE2_RX+-Pad137)") (class "Default")
      (node (ref "XTX1") (pin "137") (pinfunction "PCIE2_RX+_137") (pintype "passive+no_connect"))
    )
    (net (code "154") (name "unconnected-(XTX1B-PCIE2_RX--Pad139)") (class "Default")
      (node (ref "XTX1") (pin "139") (pinfunction "PCIE2_RX-_139") (pintype "passive+no_connect"))
    )
    (net (code "155") (name "unconnected-(XTX1B-PCIE2_TX+-Pad131)") (class "Default")
      (node (ref "XTX1") (pin "131") (pinfunction "PCIE2_TX+_131") (pintype "passive+no_connect"))
    )
    (net (code "156") (name "unconnected-(XTX1B-PCIE2_TX--Pad133)") (class "Default")
      (node (ref "XTX1") (pin "133") (pinfunction "PCIE2_TX-_133") (pintype "passive+no_connect"))
    )
    (net (code "157") (name "unconnected-(XTX1B-PCIE3_RX+-Pad115)") (class "Default")
      (node (ref "XTX1") (pin "115") (pinfunction "PCIE3_RX+_115") (pintype "passive+no_connect"))
    )
    (net (code "158") (name "unconnected-(XTX1B-PCIE3_RX--Pad117)") (class "Default")
      (node (ref "XTX1") (pin "117") (pinfunction "PCIE3_RX-_117") (pintype "passive+no_connect"))
    )
    (net (code "159") (name "unconnected-(XTX1B-PCIE3_TX+-Pad109)") (class "Default")
      (node (ref "XTX1") (pin "109") (pinfunction "PCIE3_TX+_109") (pintype "passive+no_connect"))
    )
    (net (code "160") (name "unconnected-(XTX1B-PCIE3_TX--Pad111)") (class "Default")
      (node (ref "XTX1") (pin "111") (pinfunction "PCIE3_TX-_111") (pintype "passive+no_connect"))
    )
    (net (code "161") (name "unconnected-(XTX1B-PCIE_CLK_REF+-Pad103)") (class "Default")
      (node (ref "XTX1") (pin "103") (pinfunction "PCIE_CLK_REF+_103") (pintype "passive+no_connect"))
    )
    (net (code "162") (name "unconnected-(XTX1B-PCIE_CLK_REF--Pad105)") (class "Default")
      (node (ref "XTX1") (pin "105") (pinfunction "PCIE_CLK_REF-_105") (pintype "passive+no_connect"))
    )
    (net (code "163") (name "unconnected-(XTX1B-PCI_CLKRUN#-Pad134)") (class "Default")
      (node (ref "XTX1") (pin "134") (pinfunction "PCI_CLKRUN#_134") (pintype "passive+no_connect"))
    )
    (net (code "164") (name "unconnected-(XTX1B-PCI_GNT#A-Pad164)") (class "Default")
      (node (ref "XTX1") (pin "164") (pinfunction "PCI_GNT#A_164") (pintype "passive+no_connect"))
    )
    (net (code "165") (name "unconnected-(XTX1B-PCI_REQ#A-Pad166)") (class "Default")
      (node (ref "XTX1") (pin "166") (pinfunction "PCI_REQ#A_166") (pintype "passive+no_connect"))
    )
    (net (code "166") (name "unconnected-(XTX1B-PP_TPM-Pad160)") (class "Default")
      (node (ref "XTX1") (pin "160") (pinfunction "PP_TPM_160") (pintype "passive+no_connect"))
    )
    (net (code "167") (name "unconnected-(XTX1B-RESERVED-Pad162)") (class "Default")
      (node (ref "XTX1") (pin "162") (pinfunction "RESERVED_162") (pintype "passive+no_connect"))
    )
    (net (code "168") (name "unconnected-(XTX1B-RESERVED-Pad170)") (class "Default")
      (node (ref "XTX1") (pin "170") (pinfunction "RESERVED_170") (pintype "passive+no_connect"))
    )
    (net (code "169") (name "unconnected-(XTX1B-RESERVED-Pad172)") (class "Default")
      (node (ref "XTX1") (pin "172") (pinfunction "RESERVED_172") (pintype "passive+no_connect"))
    )
    (net (code "170") (name "unconnected-(XTX1B-RESERVED-Pad176)") (class "Default")
      (node (ref "XTX1") (pin "176") (pinfunction "RESERVED_176") (pintype "passive+no_connect"))
    )
    (net (code "171") (name "unconnected-(XTX1B-RESERVED-Pad178)") (class "Default")
      (node (ref "XTX1") (pin "178") (pinfunction "RESERVED_178") (pintype "passive+no_connect"))
    )
    (net (code "172") (name "unconnected-(XTX1B-SATA1_RX+-Pad116)") (class "Default")
      (node (ref "XTX1") (pin "116") (pinfunction "SATA1_RX+_116") (pintype "passive+no_connect"))
    )
    (net (code "173") (name "unconnected-(XTX1B-SATA1_RX--Pad118)") (class "Default")
      (node (ref "XTX1") (pin "118") (pinfunction "SATA1_RX-_118") (pintype "passive+no_connect"))
    )
    (net (code "174") (name "unconnected-(XTX1B-SATA1_TX+-Pad124)") (class "Default")
      (node (ref "XTX1") (pin "124") (pinfunction "SATA1_TX+_124") (pintype "passive+no_connect"))
    )
    (net (code "175") (name "unconnected-(XTX1B-SATA1_TX--Pad122)") (class "Default")
      (node (ref "XTX1") (pin "122") (pinfunction "SATA1_TX-_122") (pintype "passive+no_connect"))
    )
    (net (code "176") (name "unconnected-(XTX1B-SATA2_RX+-Pad128)") (class "Default")
      (node (ref "XTX1") (pin "128") (pinfunction "SATA2_RX+_128") (pintype "passive+no_connect"))
    )
    (net (code "177") (name "unconnected-(XTX1B-SATA2_RX--Pad130)") (class "Default")
      (node (ref "XTX1") (pin "130") (pinfunction "SATA2_RX-_130") (pintype "passive+no_connect"))
    )
    (net (code "178") (name "unconnected-(XTX1B-SATA2_TX+-Pad140)") (class "Default")
      (node (ref "XTX1") (pin "140") (pinfunction "SATA2_TX+_140") (pintype "passive+no_connect"))
    )
    (net (code "179") (name "unconnected-(XTX1B-SATA2_TX--Pad138)") (class "Default")
      (node (ref "XTX1") (pin "138") (pinfunction "SATA2_TX-_138") (pintype "passive+no_connect"))
    )
    (net (code "180") (name "unconnected-(XTX1B-SATA3_RX+-Pad144)") (class "Default")
      (node (ref "XTX1") (pin "144") (pinfunction "SATA3_RX+_144") (pintype "passive+no_connect"))
    )
    (net (code "181") (name "unconnected-(XTX1B-SATA3_RX--Pad146)") (class "Default")
      (node (ref "XTX1") (pin "146") (pinfunction "SATA3_RX-_146") (pintype "passive+no_connect"))
    )
    (net (code "182") (name "unconnected-(XTX1B-SATA3_TX+-Pad156)") (class "Default")
      (node (ref "XTX1") (pin "156") (pinfunction "SATA3_TX+_156") (pintype "passive+no_connect"))
    )
    (net (code "183") (name "unconnected-(XTX1B-SATA3_TX--Pad154)") (class "Default")
      (node (ref "XTX1") (pin "154") (pinfunction "SATA3_TX-_154") (pintype "passive+no_connect"))
    )
    (net (code "184") (name "unconnected-(XTX1B-SLP_S3#-Pad149)") (class "Default")
      (node (ref "XTX1") (pin "149") (pinfunction "SLP_S3#_149") (pintype "passive+no_connect"))
    )
    (net (code "185") (name "unconnected-(XTX1B-SLP_S5#-Pad165)") (class "Default")
      (node (ref "XTX1") (pin "165") (pinfunction "SLP_S5#_165") (pintype "passive+no_connect"))
    )
    (net (code "186") (name "unconnected-(XTX1B-SUS_STAT#-Pad132)") (class "Default")
      (node (ref "XTX1") (pin "132") (pinfunction "SUS_STAT#_132") (pintype "passive+no_connect"))
    )
    (net (code "187") (name "unconnected-(XTX1C-ACK#{slash}DRV-Pad284)") (class "Default")
      (node (ref "XTX1") (pin "284") (pinfunction "ACK#/DRV_284") (pintype "passive+no_connect"))
    )
    (net (code "188") (name "unconnected-(XTX1C-AFD#{slash}DENSEL-Pad256)") (class "Default")
      (node (ref "XTX1") (pin "256") (pinfunction "AFD#/DENSEL_256") (pintype "passive+no_connect"))
    )
    (net (code "189") (name "unconnected-(XTX1C-BIASON-Pad245)") (class "Default")
      (node (ref "XTX1") (pin "245") (pinfunction "BIASON_245") (pintype "passive+no_connect"))
    )
    (net (code "190") (name "unconnected-(XTX1C-BLON#-Pad244)") (class "Default")
      (node (ref "XTX1") (pin "244") (pinfunction "BLON#_244") (pintype "passive+no_connect"))
    )
    (net (code "191") (name "unconnected-(XTX1C-BUSY{slash}MOT-Pad286)") (class "Default")
      (node (ref "XTX1") (pin "286") (pinfunction "BUSY/MOT_286") (pintype "passive+no_connect"))
    )
    (net (code "192") (name "unconnected-(XTX1C-C-Pad250)") (class "Default")
      (node (ref "XTX1") (pin "250") (pinfunction "C_250") (pintype "passive+no_connect"))
    )
    (net (code "193") (name "unconnected-(XTX1C-COMP-Pad247)") (class "Default")
      (node (ref "XTX1") (pin "247") (pinfunction "COMP_247") (pintype "passive+no_connect"))
    )
    (net (code "194") (name "unconnected-(XTX1C-CTS1#-Pad293)") (class "Default")
      (node (ref "XTX1") (pin "293") (pinfunction "CTS1#_293") (pintype "passive+no_connect"))
    )
    (net (code "195") (name "unconnected-(XTX1C-CTS2#-Pad275)") (class "Default")
      (node (ref "XTX1") (pin "275") (pinfunction "CTS2#_275") (pintype "passive+no_connect"))
    )
    (net (code "196") (name "unconnected-(XTX1C-DCD1#-Pad289)") (class "Default")
      (node (ref "XTX1") (pin "289") (pinfunction "DCD1#_289") (pintype "passive+no_connect"))
    )
    (net (code "197") (name "unconnected-(XTX1C-DCD2#-Pad271)") (class "Default")
      (node (ref "XTX1") (pin "271") (pinfunction "DCD2#_271") (pintype "passive+no_connect"))
    )
    (net (code "198") (name "unconnected-(XTX1C-DETECT#-Pad209)") (class "Default")
      (node (ref "XTX1") (pin "209") (pinfunction "DETECT#_209") (pintype "passive+no_connect"))
    )
    (net (code "199") (name "unconnected-(XTX1C-DIGON-Pad246)") (class "Default")
      (node (ref "XTX1") (pin "246") (pinfunction "DIGON_246") (pintype "passive+no_connect"))
    )
    (net (code "200") (name "unconnected-(XTX1C-DSR1#-Pad291)") (class "Default")
      (node (ref "XTX1") (pin "291") (pinfunction "DSR1#_291") (pintype "passive+no_connect"))
    )
    (net (code "201") (name "unconnected-(XTX1C-DSR2#-Pad273)") (class "Default")
      (node (ref "XTX1") (pin "273") (pinfunction "DSR2#_273") (pintype "passive+no_connect"))
    )
    (net (code "202") (name "unconnected-(XTX1C-DTR1#-Pad287)") (class "Default")
      (node (ref "XTX1") (pin "287") (pinfunction "DTR1#_287") (pintype "passive+no_connect"))
    )
    (net (code "203") (name "unconnected-(XTX1C-DTR2#-Pad269)") (class "Default")
      (node (ref "XTX1") (pin "269") (pinfunction "DTR2#_269") (pintype "passive+no_connect"))
    )
    (net (code "204") (name "unconnected-(XTX1C-ERR#{slash}HDSEL#-Pad260)") (class "Default")
      (node (ref "XTX1") (pin "260") (pinfunction "ERR#/HDSEL#_260") (pintype "passive+no_connect"))
    )
    (net (code "205") (name "unconnected-(XTX1C-FPDDC_CLK-Pad243)") (class "Default")
      (node (ref "XTX1") (pin "243") (pinfunction "FPDDC_CLK_243") (pintype "passive+no_connect"))
    )
    (net (code "206") (name "unconnected-(XTX1C-FPDDC_DAT-Pad241)") (class "Default")
      (node (ref "XTX1") (pin "241") (pinfunction "FPDDC_DAT_241") (pintype "passive+no_connect"))
    )
    (net (code "207") (name "unconnected-(XTX1C-INIT#{slash}DIR#-Pad264)") (class "Default")
      (node (ref "XTX1") (pin "264") (pinfunction "INIT#/DIR#_264") (pintype "passive+no_connect"))
    )
    (net (code "208") (name "unconnected-(XTX1C-IRRX-Pad259)") (class "Default")
      (node (ref "XTX1") (pin "259") (pinfunction "IRRX_259") (pintype "passive+no_connect"))
    )
    (net (code "209") (name "unconnected-(XTX1C-IRTX-Pad261)") (class "Default")
      (node (ref "XTX1") (pin "261") (pinfunction "IRTX_261") (pintype "passive+no_connect"))
    )
    (net (code "210") (name "unconnected-(XTX1C-KBCLK-Pad296)") (class "Default")
      (node (ref "XTX1") (pin "296") (pinfunction "KBCLK_296") (pintype "passive+no_connect"))
    )
    (net (code "211") (name "unconnected-(XTX1C-KBDAT-Pad298)") (class "Default")
      (node (ref "XTX1") (pin "298") (pinfunction "KBDAT_298") (pintype "passive+no_connect"))
    )
    (net (code "212") (name "unconnected-(XTX1C-LCDDO0-Pad237)") (class "Default")
      (node (ref "XTX1") (pin "237") (pinfunction "LCDDO0_237") (pintype "passive+no_connect"))
    )
    (net (code "213") (name "unconnected-(XTX1C-LCDDO1-Pad235)") (class "Default")
      (node (ref "XTX1") (pin "235") (pinfunction "LCDDO1_235") (pintype "passive+no_connect"))
    )
    (net (code "214") (name "unconnected-(XTX1C-LCDDO2-Pad238)") (class "Default")
      (node (ref "XTX1") (pin "238") (pinfunction "LCDDO2_238") (pintype "passive+no_connect"))
    )
    (net (code "215") (name "unconnected-(XTX1C-LCDDO3-Pad236)") (class "Default")
      (node (ref "XTX1") (pin "236") (pinfunction "LCDDO3_236") (pintype "passive+no_connect"))
    )
    (net (code "216") (name "unconnected-(XTX1C-LCDDO4-Pad229)") (class "Default")
      (node (ref "XTX1") (pin "229") (pinfunction "LCDDO4_229") (pintype "passive+no_connect"))
    )
    (net (code "217") (name "unconnected-(XTX1C-LCDDO5-Pad231)") (class "Default")
      (node (ref "XTX1") (pin "231") (pinfunction "LCDDO5_231") (pintype "passive+no_connect"))
    )
    (net (code "218") (name "unconnected-(XTX1C-LCDDO6-Pad232)") (class "Default")
      (node (ref "XTX1") (pin "232") (pinfunction "LCDDO6_232") (pintype "passive+no_connect"))
    )
    (net (code "219") (name "unconnected-(XTX1C-LCDDO7-Pad230)") (class "Default")
      (node (ref "XTX1") (pin "230") (pinfunction "LCDDO7_230") (pintype "passive+no_connect"))
    )
    (net (code "220") (name "unconnected-(XTX1C-LCDDO8-Pad223)") (class "Default")
      (node (ref "XTX1") (pin "223") (pinfunction "LCDDO8_223") (pintype "passive+no_connect"))
    )
    (net (code "221") (name "unconnected-(XTX1C-LCDDO9-Pad225)") (class "Default")
      (node (ref "XTX1") (pin "225") (pinfunction "LCDDO9_225") (pintype "passive+no_connect"))
    )
    (net (code "222") (name "unconnected-(XTX1C-LCDDO10-Pad226)") (class "Default")
      (node (ref "XTX1") (pin "226") (pinfunction "LCDDO10_226") (pintype "passive+no_connect"))
    )
    (net (code "223") (name "unconnected-(XTX1C-LCDDO11-Pad224)") (class "Default")
      (node (ref "XTX1") (pin "224") (pinfunction "LCDDO11_224") (pintype "passive+no_connect"))
    )
    (net (code "224") (name "unconnected-(XTX1C-LCDDO12-Pad219)") (class "Default")
      (node (ref "XTX1") (pin "219") (pinfunction "LCDDO12_219") (pintype "passive+no_connect"))
    )
    (net (code "225") (name "unconnected-(XTX1C-LCDDO13-Pad217)") (class "Default")
      (node (ref "XTX1") (pin "217") (pinfunction "LCDDO13_217") (pintype "passive+no_connect"))
    )
    (net (code "226") (name "unconnected-(XTX1C-LCDDO14-Pad220)") (class "Default")
      (node (ref "XTX1") (pin "220") (pinfunction "LCDDO14_220") (pintype "passive+no_connect"))
    )
    (net (code "227") (name "unconnected-(XTX1C-LCDDO15-Pad218)") (class "Default")
      (node (ref "XTX1") (pin "218") (pinfunction "LCDDO15_218") (pintype "passive+no_connect"))
    )
    (net (code "228") (name "unconnected-(XTX1C-LCDDO16-Pad211)") (class "Default")
      (node (ref "XTX1") (pin "211") (pinfunction "LCDDO16_211") (pintype "passive+no_connect"))
    )
    (net (code "229") (name "unconnected-(XTX1C-LCDDO17-Pad213)") (class "Default")
      (node (ref "XTX1") (pin "213") (pinfunction "LCDDO17_213") (pintype "passive+no_connect"))
    )
    (net (code "230") (name "unconnected-(XTX1C-LCDDO18-Pad212)") (class "Default")
      (node (ref "XTX1") (pin "212") (pinfunction "LCDDO18_212") (pintype "passive+no_connect"))
    )
    (net (code "231") (name "unconnected-(XTX1C-LCDDO19-Pad214)") (class "Default")
      (node (ref "XTX1") (pin "214") (pinfunction "LCDDO19_214") (pintype "passive+no_connect"))
    )
    (net (code "232") (name "unconnected-(XTX1C-LPT{slash}FLP#-Pad251)") (class "Default")
      (node (ref "XTX1") (pin "251") (pinfunction "LPT/FLP#_251") (pintype "passive+no_connect"))
    )
    (net (code "233") (name "unconnected-(XTX1C-LTGIO0-Pad242)") (class "Default")
      (node (ref "XTX1") (pin "242") (pinfunction "LTGIO0_242") (pintype "passive+no_connect"))
    )
    (net (code "234") (name "unconnected-(XTX1C-MSCLK-Pad292)") (class "Default")
      (node (ref "XTX1") (pin "292") (pinfunction "MSCLK_292") (pintype "passive+no_connect"))
    )
    (net (code "235") (name "unconnected-(XTX1C-MSDAT-Pad294)") (class "Default")
      (node (ref "XTX1") (pin "294") (pinfunction "MSDAT_294") (pintype "passive+no_connect"))
    )
    (net (code "236") (name "unconnected-(XTX1C-PD0{slash}INDEX#-Pad280)") (class "Default")
      (node (ref "XTX1") (pin "280") (pinfunction "PD0/INDEX#_280") (pintype "passive+no_connect"))
    )
    (net (code "237") (name "unconnected-(XTX1C-PD1{slash}TRK0#-Pad278)") (class "Default")
      (node (ref "XTX1") (pin "278") (pinfunction "PD1/TRK0#_278") (pintype "passive+no_connect"))
    )
    (net (code "238") (name "unconnected-(XTX1C-PD2{slash}WP#-Pad276)") (class "Default")
      (node (ref "XTX1") (pin "276") (pinfunction "PD2/WP#_276") (pintype "passive+no_connect"))
    )
    (net (code "239") (name "unconnected-(XTX1C-PD3{slash}RDATA#-Pad274)") (class "Default")
      (node (ref "XTX1") (pin "274") (pinfunction "PD3/RDATA#_274") (pintype "passive+no_connect"))
    )
    (net (code "240") (name "unconnected-(XTX1C-PD4{slash}DSKCHG#-Pad272)") (class "Default")
      (node (ref "XTX1") (pin "272") (pinfunction "PD4/DSKCHG#_272") (pintype "passive+no_connect"))
    )
    (net (code "241") (name "unconnected-(XTX1C-PD5{slash}RESERVED-Pad268)") (class "Default")
      (node (ref "XTX1") (pin "268") (pinfunction "PD5/RESERVED_268") (pintype "passive+no_connect"))
    )
    (net (code "242") (name "unconnected-(XTX1C-PD6{slash}RESERVED-Pad262)") (class "Default")
      (node (ref "XTX1") (pin "262") (pinfunction "PD6/RESERVED_262") (pintype "passive+no_connect"))
    )
    (net (code "243") (name "unconnected-(XTX1C-PD7{slash}RESERVED-Pad258)") (class "Default")
      (node (ref "XTX1") (pin "258") (pinfunction "PD7/RESERVED_258") (pintype "passive+no_connect"))
    )
    (net (code "244") (name "unconnected-(XTX1C-PE{slash}WDATA#-Pad288)") (class "Default")
      (node (ref "XTX1") (pin "288") (pinfunction "PE/WDATA#_288") (pintype "passive+no_connect"))
    )
    (net (code "245") (name "unconnected-(XTX1C-RESERVED-Pad252)") (class "Default")
      (node (ref "XTX1") (pin "252") (pinfunction "RESERVED_252") (pintype "passive+no_connect"))
    )
    (net (code "246") (name "unconnected-(XTX1C-RESERVED-Pad257)") (class "Default")
      (node (ref "XTX1") (pin "257") (pinfunction "RESERVED_257") (pintype "passive"))
    )
    (net (code "247") (name "unconnected-(XTX1C-RI1#-Pad297)") (class "Default")
      (node (ref "XTX1") (pin "297") (pinfunction "RI1#_297") (pintype "passive+no_connect"))
    )
    (net (code "248") (name "unconnected-(XTX1C-RI2#-Pad279)") (class "Default")
      (node (ref "XTX1") (pin "279") (pinfunction "RI2#_279") (pintype "passive+no_connect"))
    )
    (net (code "249") (name "unconnected-(XTX1C-RTS1#-Pad285)") (class "Default")
      (node (ref "XTX1") (pin "285") (pinfunction "RTS1#_285") (pintype "passive+no_connect"))
    )
    (net (code "250") (name "unconnected-(XTX1C-RTS2#-Pad267)") (class "Default")
      (node (ref "XTX1") (pin "267") (pinfunction "RTS2#_267") (pintype "passive+no_connect"))
    )
    (net (code "251") (name "unconnected-(XTX1C-RXD1-Pad283)") (class "Default")
      (node (ref "XTX1") (pin "283") (pinfunction "RXD1_283") (pintype "passive+no_connect"))
    )
    (net (code "252") (name "unconnected-(XTX1C-RXD2-Pad263)") (class "Default")
      (node (ref "XTX1") (pin "263") (pinfunction "RXD2_263") (pintype "passive+no_connect"))
    )
    (net (code "253") (name "unconnected-(XTX1C-SLCT{slash}WGATE#-Pad290)") (class "Default")
      (node (ref "XTX1") (pin "290") (pinfunction "SLCT/WGATE#_290") (pintype "passive+no_connect"))
    )
    (net (code "254") (name "unconnected-(XTX1C-SLIN#{slash}STEP#-Pad270)") (class "Default")
      (node (ref "XTX1") (pin "270") (pinfunction "SLIN#/STEP#_270") (pintype "passive+no_connect"))
    )
    (net (code "255") (name "unconnected-(XTX1C-STB#{slash}RESERVED-Pad255)") (class "Default")
      (node (ref "XTX1") (pin "255") (pinfunction "STB#/RESERVED_255") (pintype "passive+no_connect"))
    )
    (net (code "256") (name "unconnected-(XTX1C-SYNC-Pad249)") (class "Default")
      (node (ref "XTX1") (pin "249") (pinfunction "SYNC_249") (pintype "passive+no_connect"))
    )
    (net (code "257") (name "unconnected-(XTX1C-TXD1-Pad295)") (class "Default")
      (node (ref "XTX1") (pin "295") (pinfunction "TXD1_295") (pintype "passive+no_connect"))
    )
    (net (code "258") (name "unconnected-(XTX1C-TXD2-Pad277)") (class "Default")
      (node (ref "XTX1") (pin "277") (pinfunction "TXD2_277") (pintype "passive+no_connect"))
    )
    (net (code "259") (name "unconnected-(XTX1C-Y-Pad248)") (class "Default")
      (node (ref "XTX1") (pin "248") (pinfunction "Y_248") (pintype "passive+no_connect"))
    )
    (net (code "260") (name "unconnected-(XTX1D-5V_SB-Pad303)") (class "Default")
      (node (ref "XTX1") (pin "303") (pinfunction "5V_SB_303") (pintype "passive+no_connect"))
    )
    (net (code "261") (name "unconnected-(XTX1D-BATLOW#-Pad341)") (class "Default")
      (node (ref "XTX1") (pin "341") (pinfunction "BATLOW#_341") (pintype "passive"))
    )
    (net (code "262") (name "unconnected-(XTX1D-CBLID_P#-Pad390)") (class "Default")
      (node (ref "XTX1") (pin "390") (pinfunction "CBLID_P#_390") (pintype "passive+no_connect"))
    )
    (net (code "263") (name "unconnected-(XTX1D-DASP_S-Pad328)") (class "Default")
      (node (ref "XTX1") (pin "328") (pinfunction "DASP_S_328") (pintype "passive+no_connect"))
    )
    (net (code "264") (name "unconnected-(XTX1D-EXT_PRG-Pad315)") (class "Default")
      (node (ref "XTX1") (pin "315") (pinfunction "EXT_PRG_315") (pintype "passive+no_connect"))
    )
    (net (code "265") (name "unconnected-(XTX1D-GPCS#-Pad320)") (class "Default")
      (node (ref "XTX1") (pin "320") (pinfunction "GPCS#_320") (pintype "passive+no_connect"))
    )
    (net (code "266") (name "unconnected-(XTX1D-HDRST#-Pad398)") (class "Default")
      (node (ref "XTX1") (pin "398") (pinfunction "HDRST#_398") (pintype "passive+no_connect"))
    )
    (net (code "267") (name "unconnected-(XTX1D-I2CLK-Pad316)") (class "Default")
      (node (ref "XTX1") (pin "316") (pinfunction "I2CLK_316") (pintype "passive+no_connect"))
    )
    (net (code "268") (name "unconnected-(XTX1D-I2DAT-Pad322)") (class "Default")
      (node (ref "XTX1") (pin "322") (pinfunction "I2DAT_322") (pintype "passive+no_connect"))
    )
    (net (code "269") (name "unconnected-(XTX1D-KBINH#-Pad309)") (class "Default")
      (node (ref "XTX1") (pin "309") (pinfunction "KBINH#_309") (pintype "passive+no_connect"))
    )
    (net (code "270") (name "unconnected-(XTX1D-PDIAG_S-Pad335)") (class "Default")
      (node (ref "XTX1") (pin "335") (pinfunction "PDIAG_S_335") (pintype "passive+no_connect"))
    )
    (net (code "271") (name "unconnected-(XTX1D-PIDE_A0-Pad338)") (class "Default")
      (node (ref "XTX1") (pin "338") (pinfunction "PIDE_A0_338") (pintype "passive+no_connect"))
    )
    (net (code "272") (name "unconnected-(XTX1D-PIDE_A1-Pad340)") (class "Default")
      (node (ref "XTX1") (pin "340") (pinfunction "PIDE_A1_340") (pintype "passive+no_connect"))
    )
    (net (code "273") (name "unconnected-(XTX1D-PIDE_A2-Pad336)") (class "Default")
      (node (ref "XTX1") (pin "336") (pinfunction "PIDE_A2_336") (pintype "passive+no_connect"))
    )
    (net (code "274") (name "unconnected-(XTX1D-PIDE_AK#-Pad346)") (class "Default")
      (node (ref "XTX1") (pin "346") (pinfunction "PIDE_AK#_346") (pintype "passive+no_connect"))
    )
    (net (code "275") (name "unconnected-(XTX1D-PIDE_CS1#-Pad332)") (class "Default")
      (node (ref "XTX1") (pin "332") (pinfunction "PIDE_CS1#_332") (pintype "passive+no_connect"))
    )
    (net (code "276") (name "unconnected-(XTX1D-PIDE_CS3#-Pad330)") (class "Default")
      (node (ref "XTX1") (pin "330") (pinfunction "PIDE_CS3#_330") (pintype "passive+no_connect"))
    )
    (net (code "277") (name "unconnected-(XTX1D-PIDE_D0-Pad360)") (class "Default")
      (node (ref "XTX1") (pin "360") (pinfunction "PIDE_D0_360") (pintype "passive+no_connect"))
    )
    (net (code "278") (name "unconnected-(XTX1D-PIDE_D1-Pad364)") (class "Default")
      (node (ref "XTX1") (pin "364") (pinfunction "PIDE_D1_364") (pintype "passive+no_connect"))
    )
    (net (code "279") (name "unconnected-(XTX1D-PIDE_D2-Pad370)") (class "Default")
      (node (ref "XTX1") (pin "370") (pinfunction "PIDE_D2_370") (pintype "passive+no_connect"))
    )
    (net (code "280") (name "unconnected-(XTX1D-PIDE_D3-Pad374)") (class "Default")
      (node (ref "XTX1") (pin "374") (pinfunction "PIDE_D3_374") (pintype "passive+no_connect"))
    )
    (net (code "281") (name "unconnected-(XTX1D-PIDE_D4-Pad378)") (class "Default")
      (node (ref "XTX1") (pin "378") (pinfunction "PIDE_D4_378") (pintype "passive+no_connect"))
    )
    (net (code "282") (name "unconnected-(XTX1D-PIDE_D5-Pad384)") (class "Default")
      (node (ref "XTX1") (pin "384") (pinfunction "PIDE_D5_384") (pintype "passive+no_connect"))
    )
    (net (code "283") (name "unconnected-(XTX1D-PIDE_D6-Pad388)") (class "Default")
      (node (ref "XTX1") (pin "388") (pinfunction "PIDE_D6_388") (pintype "passive+no_connect"))
    )
    (net (code "284") (name "unconnected-(XTX1D-PIDE_D7-Pad396)") (class "Default")
      (node (ref "XTX1") (pin "396") (pinfunction "PIDE_D7_396") (pintype "passive+no_connect"))
    )
    (net (code "285") (name "unconnected-(XTX1D-PIDE_D8-Pad392)") (class "Default")
      (node (ref "XTX1") (pin "392") (pinfunction "PIDE_D8_392") (pintype "passive+no_connect"))
    )
    (net (code "286") (name "unconnected-(XTX1D-PIDE_D9-Pad386)") (class "Default")
      (node (ref "XTX1") (pin "386") (pinfunction "PIDE_D9_386") (pintype "passive+no_connect"))
    )
    (net (code "287") (name "unconnected-(XTX1D-PIDE_D10-Pad380)") (class "Default")
      (node (ref "XTX1") (pin "380") (pinfunction "PIDE_D10_380") (pintype "passive+no_connect"))
    )
    (net (code "288") (name "unconnected-(XTX1D-PIDE_D11-Pad376)") (class "Default")
      (node (ref "XTX1") (pin "376") (pinfunction "PIDE_D11_376") (pintype "passive+no_connect"))
    )
    (net (code "289") (name "unconnected-(XTX1D-PIDE_D12-Pad372)") (class "Default")
      (node (ref "XTX1") (pin "372") (pinfunction "PIDE_D12_372") (pintype "passive+no_connect"))
    )
    (net (code "290") (name "unconnected-(XTX1D-PIDE_D13-Pad368)") (class "Default")
      (node (ref "XTX1") (pin "368") (pinfunction "PIDE_D13_368") (pintype "passive+no_connect"))
    )
    (net (code "291") (name "unconnected-(XTX1D-PIDE_D14-Pad362)") (class "Default")
      (node (ref "XTX1") (pin "362") (pinfunction "PIDE_D14_362") (pintype "passive+no_connect"))
    )
    (net (code "292") (name "unconnected-(XTX1D-PIDE_D15-Pad358)") (class "Default")
      (node (ref "XTX1") (pin "358") (pinfunction "PIDE_D15_358") (pintype "passive+no_connect"))
    )
    (net (code "293") (name "unconnected-(XTX1D-PIDE_DRQ-Pad356)") (class "Default")
      (node (ref "XTX1") (pin "356") (pinfunction "PIDE_DRQ_356") (pintype "passive"))
    )
    (net (code "294") (name "unconnected-(XTX1D-PIDE_INTRQ-Pad344)") (class "Default")
      (node (ref "XTX1") (pin "344") (pinfunction "PIDE_INTRQ_344") (pintype "passive+no_connect"))
    )
    (net (code "295") (name "unconnected-(XTX1D-PIDE_IOR#-Pad352)") (class "Default")
      (node (ref "XTX1") (pin "352") (pinfunction "PIDE_IOR#_352") (pintype "passive+no_connect"))
    )
    (net (code "296") (name "unconnected-(XTX1D-PIDE_IOW#-Pad354)") (class "Default")
      (node (ref "XTX1") (pin "354") (pinfunction "PIDE_IOW#_354") (pintype "passive+no_connect"))
    )
    (net (code "297") (name "unconnected-(XTX1D-PIDE_RDY-Pad348)") (class "Default")
      (node (ref "XTX1") (pin "348") (pinfunction "PIDE_RDY_348") (pintype "passive+no_connect"))
    )
    (net (code "298") (name "unconnected-(XTX1D-PS_ON#-Pad305)") (class "Default")
      (node (ref "XTX1") (pin "305") (pinfunction "PS_ON#_305") (pintype "passive+no_connect"))
    )
    (net (code "299") (name "unconnected-(XTX1D-PWRBTN#-Pad307)") (class "Default")
      (node (ref "XTX1") (pin "307") (pinfunction "PWRBTN#_307") (pintype "passive+no_connect"))
    )
    (net (code "300") (name "unconnected-(XTX1D-ROMKBCS#-Pad313)") (class "Default")
      (node (ref "XTX1") (pin "313") (pinfunction "ROMKBCS#_313") (pintype "passive+no_connect"))
    )
    (net (code "301") (name "unconnected-(XTX1D-SIDE_A0-Pad331)") (class "Default")
      (node (ref "XTX1") (pin "331") (pinfunction "SIDE_A0_331") (pintype "passive+no_connect"))
    )
    (net (code "302") (name "unconnected-(XTX1D-SIDE_A1-Pad337)") (class "Default")
      (node (ref "XTX1") (pin "337") (pinfunction "SIDE_A1_337") (pintype "passive+no_connect"))
    )
    (net (code "303") (name "unconnected-(XTX1D-SIDE_A2-Pad329)") (class "Default")
      (node (ref "XTX1") (pin "329") (pinfunction "SIDE_A2_329") (pintype "passive+no_connect"))
    )
    (net (code "304") (name "unconnected-(XTX1D-SIDE_AK#-Pad343)") (class "Default")
      (node (ref "XTX1") (pin "343") (pinfunction "SIDE_AK#_343") (pintype "passive+no_connect"))
    )
    (net (code "305") (name "unconnected-(XTX1D-SIDE_CS1#-Pad327)") (class "Default")
      (node (ref "XTX1") (pin "327") (pinfunction "SIDE_CS1#_327") (pintype "passive+no_connect"))
    )
    (net (code "306") (name "unconnected-(XTX1D-SIDE_CS3#-Pad325)") (class "Default")
      (node (ref "XTX1") (pin "325") (pinfunction "SIDE_CS3#_325") (pintype "passive+no_connect"))
    )
    (net (code "307") (name "unconnected-(XTX1D-SIDE_D0-Pad357)") (class "Default")
      (node (ref "XTX1") (pin "357") (pinfunction "SIDE_D0_357") (pintype "passive+no_connect"))
    )
    (net (code "308") (name "unconnected-(XTX1D-SIDE_D1-Pad361)") (class "Default")
      (node (ref "XTX1") (pin "361") (pinfunction "SIDE_D1_361") (pintype "passive+no_connect"))
    )
    (net (code "309") (name "unconnected-(XTX1D-SIDE_D2-Pad367)") (class "Default")
      (node (ref "XTX1") (pin "367") (pinfunction "SIDE_D2_367") (pintype "passive+no_connect"))
    )
    (net (code "310") (name "unconnected-(XTX1D-SIDE_D3-Pad371)") (class "Default")
      (node (ref "XTX1") (pin "371") (pinfunction "SIDE_D3_371") (pintype "passive+no_connect"))
    )
    (net (code "311") (name "unconnected-(XTX1D-SIDE_D4-Pad375)") (class "Default")
      (node (ref "XTX1") (pin "375") (pinfunction "SIDE_D4_375") (pintype "passive+no_connect"))
    )
    (net (code "312") (name "unconnected-(XTX1D-SIDE_D5-Pad379)") (class "Default")
      (node (ref "XTX1") (pin "379") (pinfunction "SIDE_D5_379") (pintype "passive+no_connect"))
    )
    (net (code "313") (name "unconnected-(XTX1D-SIDE_D6-Pad385)") (class "Default")
      (node (ref "XTX1") (pin "385") (pinfunction "SIDE_D6_385") (pintype "passive+no_connect"))
    )
    (net (code "314") (name "unconnected-(XTX1D-SIDE_D7-Pad394)") (class "Default")
      (node (ref "XTX1") (pin "394") (pinfunction "SIDE_D7_394") (pintype "passive+no_connect"))
    )
    (net (code "315") (name "unconnected-(XTX1D-SIDE_D8-Pad387)") (class "Default")
      (node (ref "XTX1") (pin "387") (pinfunction "SIDE_D8_387") (pintype "passive+no_connect"))
    )
    (net (code "316") (name "unconnected-(XTX1D-SIDE_D9-Pad383)") (class "Default")
      (node (ref "XTX1") (pin "383") (pinfunction "SIDE_D9_383") (pintype "passive+no_connect"))
    )
    (net (code "317") (name "unconnected-(XTX1D-SIDE_D10-Pad377)") (class "Default")
      (node (ref "XTX1") (pin "377") (pinfunction "SIDE_D10_377") (pintype "passive+no_connect"))
    )
    (net (code "318") (name "unconnected-(XTX1D-SIDE_D11-Pad373)") (class "Default")
      (node (ref "XTX1") (pin "373") (pinfunction "SIDE_D11_373") (pintype "passive+no_connect"))
    )
    (net (code "319") (name "unconnected-(XTX1D-SIDE_D12-Pad369)") (class "Default")
      (node (ref "XTX1") (pin "369") (pinfunction "SIDE_D12_369") (pintype "passive+no_connect"))
    )
    (net (code "320") (name "unconnected-(XTX1D-SIDE_D13-Pad363)") (class "Default")
      (node (ref "XTX1") (pin "363") (pinfunction "SIDE_D13_363") (pintype "passive+no_connect"))
    )
    (net (code "321") (name "unconnected-(XTX1D-SIDE_D14-Pad359)") (class "Default")
      (node (ref "XTX1") (pin "359") (pinfunction "SIDE_D14_359") (pintype "passive+no_connect"))
    )
    (net (code "322") (name "unconnected-(XTX1D-SIDE_D15-Pad355)") (class "Default")
      (node (ref "XTX1") (pin "355") (pinfunction "SIDE_D15_355") (pintype "passive+no_connect"))
    )
    (net (code "323") (name "unconnected-(XTX1D-SIDE_DRQ-Pad353)") (class "Default")
      (node (ref "XTX1") (pin "353") (pinfunction "SIDE_DRQ_353") (pintype "passive+no_connect"))
    )
    (net (code "324") (name "unconnected-(XTX1D-SIDE_INTRQ-Pad339)") (class "Default")
      (node (ref "XTX1") (pin "339") (pinfunction "SIDE_INTRQ_339") (pintype "passive+no_connect"))
    )
    (net (code "325") (name "unconnected-(XTX1D-SIDE_IOR#-Pad347)") (class "Default")
      (node (ref "XTX1") (pin "347") (pinfunction "SIDE_IOR#_347") (pintype "passive+no_connect"))
    )
    (net (code "326") (name "unconnected-(XTX1D-SIDE_IOW#-Pad351)") (class "Default")
      (node (ref "XTX1") (pin "351") (pinfunction "SIDE_IOW#_351") (pintype "passive+no_connect"))
    )
    (net (code "327") (name "unconnected-(XTX1D-SIDE_RDY-Pad345)") (class "Default")
      (node (ref "XTX1") (pin "345") (pinfunction "SIDE_RDY_345") (pintype "passive+no_connect"))
    )
    (net (code "328") (name "unconnected-(XTX1D-SMBALRT#-Pad326)") (class "Default")
      (node (ref "XTX1") (pin "326") (pinfunction "SMBALRT#_326") (pintype "passive+no_connect"))
    )
    (net (code "329") (name "unconnected-(XTX1D-SMBCLK-Pad323)") (class "Default")
      (node (ref "XTX1") (pin "323") (pinfunction "SMBCLK_323") (pintype "passive+no_connect"))
    )
    (net (code "330") (name "unconnected-(XTX1D-SMBDATA-Pad324)") (class "Default")
      (node (ref "XTX1") (pin "324") (pinfunction "SMBDATA_324") (pintype "passive+no_connect"))
    )
    (net (code "331") (name "unconnected-(XTX1D-SPEAKER-Pad306)") (class "Default")
      (node (ref "XTX1") (pin "306") (pinfunction "SPEAKER_306") (pintype "passive+no_connect"))
    )
    (net (code "332") (name "unconnected-(btnReset-Pad2)") (class "Default")
      (node (ref "btnReset") (pin "2") (pinfunction "2_2") (pintype "passive+no_connect"))
    )
    (net (code "333") (name "unconnected-(btnReset-Pad3)") (class "Default")
      (node (ref "btnReset") (pin "3") (pinfunction "3_3") (pintype "passive+no_connect"))
    )
  )
)
